# DCDC.net
KiCad netlist of a schematic drawn in Altium Designer
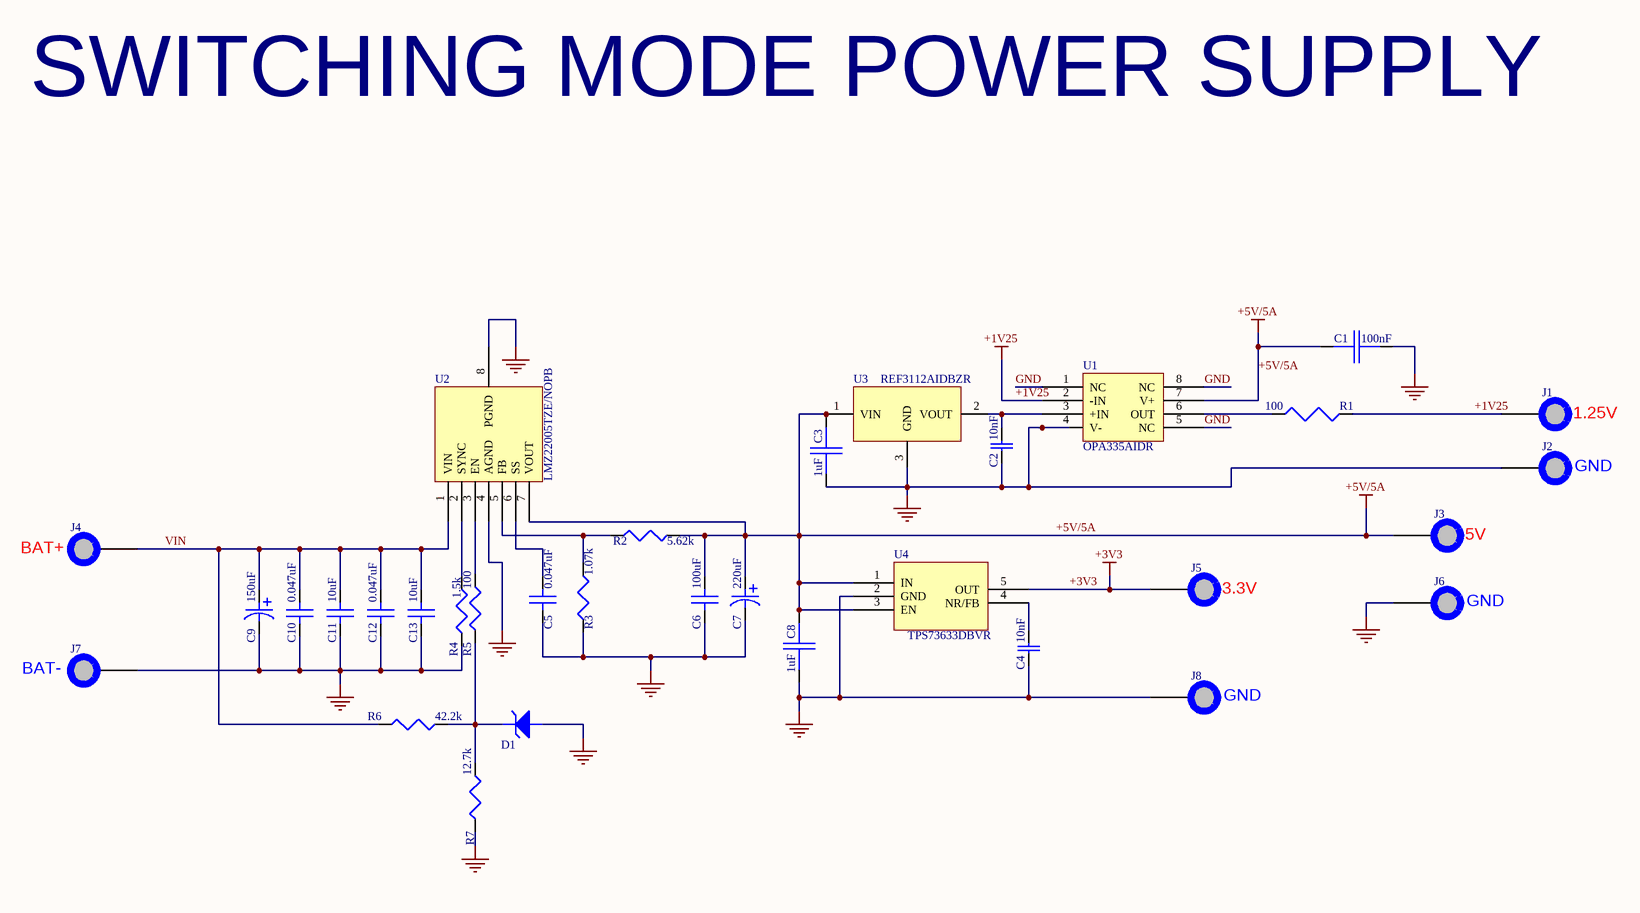
[diagram p0: DCDC.SchDoc]

(export (version "E")
  (design (tool "Eeschema 10.0.6"))
  (components
    (comp (ref "C1")
      (value "100nF")
      (footprint "C0603")
      (description "CAP CER 0.1UF 25V X7R 0603")
      (fields
        (field (name "MANUFACTURER") "Murata Electronics North America")
        (field (name "MANUFACTURER PART NUMBER") "GRM188R71E104KA01D")
      )
      (libsource (lib "EMG") (part "GRM188R71E104KA01D"))
    )
    (comp (ref "C2")
      (value "10nF")
      (footprint "C0805")
      (description "CAP CER 10000PF 50V X7R 0805")
      (fields
        (field (name "MANUFACTURER") "Murata Electronics North America")
        (field (name "MANUFACTURER PART NUMBER") "GRM216R71H103KA01D")
      )
      (libsource (lib "ISL") (part "GRM216R71H103KA01D"))
    )
    (comp (ref "C3")
      (value "1uF")
      (footprint "C0603")
      (description "CAP CER 1UF 25V X5R 0603")
      (fields
        (field (name "MANUFACTURER") "Murata Electronics North America")
        (field (name "MANUFACTURER PART NUMBER") "GRM188R61E105KA12D")
      )
      (libsource (lib "EMG") (part "GRM188R61E105KA12D"))
    )
    (comp (ref "C4")
      (value "10nF")
      (footprint "C0805")
      (description "CAP CER 10000PF 50V X7R 0805")
      (fields
        (field (name "MANUFACTURER") "Murata Electronics North America")
        (field (name "MANUFACTURER PART NUMBER") "GRM216R71H103KA01D")
      )
      (libsource (lib "ISL") (part "GRM216R71H103KA01D"))
    )
    (comp (ref "C5")
      (value "0.047uF")
      (footprint "C1206")
      (description "CAP CER 0.47UF 50V X7R 1206")
      (fields
        (field (name "MANUFACTURER") "Kemet")
        (field (name "MANUFACTURER PART NUMBER") "C1206C474K5RACTU")
      )
      (libsource (lib "DCDC") (part "C1206C474K5RACTU"))
    )
    (comp (ref "C6")
      (value "100uF")
      (footprint "C1210")
      (description "CAP CER 100UF 6.3V X5R 1210")
      (fields
        (field (name "MANUFACTURER") "TDK Corporation")
        (field (name "MANUFACTURER PART NUMBER") "C3225X5R0J107M250AC")
      )
      (libsource (lib "DCDC") (part "C3225X5R0J107M250AC"))
    )
    (comp (ref "C7")
      (value "220uF")
      (footprint "EEF-UE")
      (description "CAP POLYMER 220UF 20% 6.3V SMD")
      (fields
        (field (name "MANUFACTURER") "Panasonic Electronic Components")
        (field (name "MANUFACTURER PART NUMBER") "EEF-UE0J221LR")
      )
      (libsource (lib "DCDC") (part "EEF-UE0J221LR"))
    )
    (comp (ref "C8")
      (value "1uF")
      (footprint "C0603")
      (description "CAP CER 1UF 25V X5R 0603")
      (fields
        (field (name "MANUFACTURER") "Murata Electronics North America")
        (field (name "MANUFACTURER PART NUMBER") "GRM188R61E105KA12D")
      )
      (libsource (lib "EMG") (part "GRM188R61E105KA12D"))
    )
    (comp (ref "C9")
      (value "150uF")
      (footprint "FK-G")
      (description "CAP ALUM 150UF 20% 50V SMD")
      (fields
        (field (name "MANUFACTURER") "Panasonic Electronic Components")
        (field (name "MANUFACTURER PART NUMBER") "EEE-FK1H151P")
      )
      (libsource (lib "DCDC") (part "EEE-FK1H151P"))
    )
    (comp (ref "C10")
      (value "0.047uF")
      (footprint "C1206")
      (description "CAP CER 0.47UF 50V X7R 1206")
      (fields
        (field (name "MANUFACTURER") "Kemet")
        (field (name "MANUFACTURER PART NUMBER") "C1206C474K5RACTU")
      )
      (libsource (lib "DCDC") (part "C1206C474K5RACTU"))
    )
    (comp (ref "C11")
      (value "10uF")
      (footprint "C1206")
      (description "CAP CER 10UF 50V X5R 1206")
      (fields
        (field (name "MANUFACTURER") "Murata Electronics North America")
        (field (name "MANUFACTURER PART NUMBER") "GRM31CR61H106KA12L")
      )
      (libsource (lib "DCDC") (part "GRM31CR61H106KA12L"))
    )
    (comp (ref "C12")
      (value "0.047uF")
      (footprint "C1206")
      (description "CAP CER 0.47UF 50V X7R 1206")
      (fields
        (field (name "MANUFACTURER") "Kemet")
        (field (name "MANUFACTURER PART NUMBER") "C1206C474K5RACTU")
      )
      (libsource (lib "DCDC") (part "C1206C474K5RACTU"))
    )
    (comp (ref "C13")
      (value "10uF")
      (footprint "C1206")
      (description "CAP CER 10UF 50V X5R 1206")
      (fields
        (field (name "MANUFACTURER") "Murata Electronics North America")
        (field (name "MANUFACTURER PART NUMBER") "GRM31CR61H106KA12L")
      )
      (libsource (lib "DCDC") (part "GRM31CR61H106KA12L"))
    )
    (comp (ref "D1")
      (value "MMSZ5231BS-7-F")
      (footprint "SOD323")
      (description "DIODE ZENER 5.1V 200MW SOD323")
      (fields (field (name "MANUFACTURER") "Diodes Incorporated") (field (name "TOLERANCE") "±5%"))
      (libsource (lib "DCDC") (part "MMSZ5231BS-7-F"))
    )
    (comp (ref "J1")
      (value "PAD_4mmx1.5mm_Hole")
      (footprint "PAD_WITH_HOLE_4x1mm")
      (description "Pad 4mm x 1.5mm with hole")
      (libsource (lib "ISL") (part "PAD_4mmx1.5mm_Hole"))
    )
    (comp (ref "J2")
      (value "PAD_4mmx1.5mm_Hole")
      (footprint "PAD_WITH_HOLE_4x1mm")
      (description "Pad 4mm x 1.5mm with hole")
      (libsource (lib "ISL") (part "PAD_4mmx1.5mm_Hole"))
    )
    (comp (ref "J3")
      (value "PAD_4mmx1.5mm_Hole")
      (footprint "PAD_WITH_HOLE_4x1mm")
      (description "Pad 4mm x 1.5mm with hole")
      (libsource (lib "ISL") (part "PAD_4mmx1.5mm_Hole"))
    )
    (comp (ref "J4")
      (value "PAD_4mmx1.5mm_Hole")
      (footprint "PAD_WITH_HOLE_4x1mm")
      (description "Pad 4mm x 1.5mm with hole")
      (libsource (lib "ISL") (part "PAD_4mmx1.5mm_Hole"))
    )
    (comp (ref "J5")
      (value "PAD_4mmx1.5mm_Hole")
      (footprint "PAD_WITH_HOLE_4x1mm")
      (description "Pad 4mm x 1.5mm with hole")
      (libsource (lib "ISL") (part "PAD_4mmx1.5mm_Hole"))
    )
    (comp (ref "J6")
      (value "PAD_4mmx1.5mm_Hole")
      (footprint "PAD_WITH_HOLE_4x1mm")
      (description "Pad 4mm x 1.5mm with hole")
      (libsource (lib "ISL") (part "PAD_4mmx1.5mm_Hole"))
    )
    (comp (ref "J7")
      (value "PAD_4mmx1.5mm_Hole")
      (footprint "PAD_WITH_HOLE_4x1mm")
      (description "Pad 4mm x 1.5mm with hole")
      (libsource (lib "ISL") (part "PAD_4mmx1.5mm_Hole"))
    )
    (comp (ref "J8")
      (value "PAD_4mmx1.5mm_Hole")
      (footprint "PAD_WITH_HOLE_4x1mm")
      (description "Pad 4mm x 1.5mm with hole")
      (libsource (lib "ISL") (part "PAD_4mmx1.5mm_Hole"))
    )
    (comp (ref "R1")
      (value "100")
      (footprint "R0603")
      (description "RES SMD 100 OHM 1% 1/10W 0603")
      (fields
        (field (name "MANUFACTURER") "Panasonic Electronic Components")
        (field (name "MANUFACTURER PART NUMBER") "ERJ-3EKF1000V")
      )
      (libsource (lib "EMG") (part "ERJ-3EKF1000V"))
    )
    (comp (ref "R2")
      (value "5.62k")
      (footprint "R0805")
      (description "RES SMD 5.62K OHM 1% 1/3W 0805")
      (fields
        (field (name "MANUFACTURER") "Vishay Dale")
        (field (name "MANUFACTURER PART NUMBER") "CRCW08055K62FKEAHP")
      )
      (libsource (lib "DCDC") (part "CRCW08055K62FKEAHP"))
    )
    (comp (ref "R3")
      (value "1.07k")
      (footprint "R0805")
      (description "RES SMD 1.07K OHM 1% 1/8W 0805")
      (fields
        (field (name "MANUFACTURER") "Panasonic Electronic Components")
        (field (name "MANUFACTURER PART NUMBER") "ERJ-6ENF1071V")
      )
      (libsource (lib "DCDC") (part "ERJ-6ENF1071V"))
    )
    (comp (ref "R4")
      (value "1.5k")
      (footprint "R0805")
      (description "RES SMD 1.5K OHM 1% 1/8W 0805")
      (fields
        (field (name "MANUFACTURER") "Panasonic Electronic Components")
        (field (name "MANUFACTURER PART NUMBER") "ERJ-6ENF1501V")
      )
      (libsource (lib "DCDC") (part "ERJ-6ENF1501V"))
    )
    (comp (ref "R5")
      (value "100")
      (footprint "R0805")
      (description "RES SMD 100 OHM 1% 1/8W 0805")
      (fields
        (field (name "MANUFACTURER") "Vishay Dale")
        (field (name "MANUFACTURER PART NUMBER") "RCA0805100RFKEA")
      )
      (libsource (lib "DCDC") (part "RCA0805100RFKEA"))
    )
    (comp (ref "R6")
      (value "42.2k")
      (footprint "R0805")
      (description "RES SMD 42.2K OHM 1% 1/8W 0805")
      (fields
        (field (name "MANUFACTURER") "Panasonic Electronic Components")
        (field (name "MANUFACTURER PART NUMBER") "ERJ-6ENF4222V")
      )
      (libsource (lib "DCDC") (part "ERJ-6ENF4222V"))
    )
    (comp (ref "R7")
      (value "12.7k")
      (footprint "R0805")
      (description "RES SMD 12.7K OHM 1% 1/8W 0805")
      (fields
        (field (name "MANUFACTURER") "Panasonic Electronic Components")
        (field (name "MANUFACTURER PART NUMBER") "ERJ-6ENF1272V")
      )
      (libsource (lib "DCDC") (part "ERJ-6ENF1272V"))
    )
    (comp (ref "U1")
      (value "OPA335AIDR")
      (footprint "SO-8")
      (description "IC OPAMP CHOPPER 2MHZ RRO 8SOIC")
      (fields (field (name "MANUFACTURER") "Texas Instruments"))
      (libsource (lib "DCDC") (part "OPA335AIDR"))
    )
    (comp (ref "U2")
      (value "LMZ22005TZE/NOPB")
      (footprint "NDW0007A")
      (description "IC BUCK SYNC 20V 5A TO-PMOD-7")
      (fields (field (name "MANUFACTURER") "Texas Instruments"))
      (libsource (lib "DCDC") (part "LMZ22005TZE/NOPB"))
    )
    (comp (ref "U3")
      (value "REF3112AIDBZR")
      (footprint "SOT-23")
      (description "IC VREF SERIES 1.25V SOT23-3")
      (fields (field (name "MANUFACTURER") "Texas Instruments") (field (name "TOLERANCE") "±0.2%"))
      (libsource (lib "DCDC") (part "REF3112AIDBZR"))
    )
    (comp (ref "U4")
      (value "TPS73633DBVR")
      (footprint "SOT23-5")
      (description "IC REG LDO 3.3V 0.4A SOT23-5")
      (fields (field (name "MANUFACTURER") "Texas Instruments"))
      (libsource (lib "DCDC") (part "TPS73633DBVR"))
    )
  )
  (nets
    (net (code "1") (name "+1V25") (class "Default")
      (node (ref "J1") (pin "1") (pinfunction "1_1") (pintype "passive"))
      (node (ref "R1") (pin "1") (pinfunction "1_1") (pintype "passive"))
      (node (ref "U1") (pin "2") (pinfunction "-IN_2") (pintype "passive"))
    )
    (net (code "2") (name "+3V3") (class "Default")
      (node (ref "J5") (pin "1") (pinfunction "1_1") (pintype "passive"))
      (node (ref "U4") (pin "5") (pinfunction "OUT_5") (pintype "passive"))
    )
    (net (code "3") (name "+5V{slash}5A") (class "Default")
      (node (ref "C1") (pin "2") (pinfunction "2_2") (pintype "passive"))
      (node (ref "C3") (pin "2") (pinfunction "2_2") (pintype "passive"))
      (node (ref "C6") (pin "1") (pinfunction "1_1") (pintype "passive"))
      (node (ref "C7") (pin "1") (pinfunction "1_1") (pintype "passive"))
      (node (ref "C8") (pin "2") (pinfunction "2_2") (pintype "passive"))
      (node (ref "J3") (pin "1") (pinfunction "1_1") (pintype "passive"))
      (node (ref "R2") (pin "2") (pinfunction "2_2") (pintype "passive"))
      (node (ref "U1") (pin "7") (pinfunction "V+_7") (pintype "passive"))
      (node (ref "U2") (pin "7") (pinfunction "VOUT_7") (pintype "passive"))
      (node (ref "U3") (pin "1") (pinfunction "VIN_1") (pintype "passive"))
      (node (ref "U4") (pin "1") (pinfunction "IN_1") (pintype "passive"))
      (node (ref "U4") (pin "3") (pinfunction "EN_3") (pintype "passive"))
    )
    (net (code "4") (name "/VIN") (class "Default")
      (node (ref "C10") (pin "1") (pinfunction "1_1") (pintype "passive"))
      (node (ref "C11") (pin "2") (pinfunction "2_2") (pintype "passive"))
      (node (ref "C12") (pin "1") (pinfunction "1_1") (pintype "passive"))
      (node (ref "C13") (pin "2") (pinfunction "2_2") (pintype "passive"))
      (node (ref "C9") (pin "1") (pinfunction "1_1") (pintype "passive"))
      (node (ref "J4") (pin "1") (pinfunction "1_1") (pintype "passive"))
      (node (ref "R6") (pin "1") (pinfunction "1_1") (pintype "passive"))
      (node (ref "U2") (pin "1") (pinfunction "VIN_1") (pintype "passive"))
    )
    (net (code "5") (name "GND") (class "Default")
      (node (ref "C1") (pin "1") (pinfunction "1_1") (pintype "passive"))
      (node (ref "C10") (pin "2") (pinfunction "2_2") (pintype "passive"))
      (node (ref "C11") (pin "1") (pinfunction "1_1") (pintype "passive"))
      (node (ref "C12") (pin "2") (pinfunction "2_2") (pintype "passive"))
      (node (ref "C13") (pin "1") (pinfunction "1_1") (pintype "passive"))
      (node (ref "C2") (pin "1") (pinfunction "1_1") (pintype "passive"))
      (node (ref "C3") (pin "1") (pinfunction "1_1") (pintype "passive"))
      (node (ref "C4") (pin "1") (pinfunction "1_1") (pintype "passive"))
      (node (ref "C5") (pin "2") (pinfunction "2_2") (pintype "passive"))
      (node (ref "C6") (pin "2") (pinfunction "2_2") (pintype "passive"))
      (node (ref "C7") (pin "2") (pinfunction "2_2") (pintype "passive"))
      (node (ref "C8") (pin "1") (pinfunction "1_1") (pintype "passive"))
      (node (ref "C9") (pin "2") (pinfunction "2_2") (pintype "passive"))
      (node (ref "D1") (pin "1") (pinfunction "1_1") (pintype "passive"))
      (node (ref "J2") (pin "1") (pinfunction "1_1") (pintype "passive"))
      (node (ref "J6") (pin "1") (pinfunction "1_1") (pintype "passive"))
      (node (ref "J7") (pin "1") (pinfunction "1_1") (pintype "passive"))
      (node (ref "J8") (pin "1") (pinfunction "1_1") (pintype "passive"))
      (node (ref "R3") (pin "1") (pinfunction "1_1") (pintype "passive"))
      (node (ref "R4") (pin "1") (pinfunction "1_1") (pintype "passive"))
      (node (ref "R7") (pin "2") (pinfunction "2_2") (pintype "passive"))
      (node (ref "U1") (pin "1") (pinfunction "NC_1") (pintype "passive"))
      (node (ref "U1") (pin "4") (pinfunction "V-_4") (pintype "passive"))
      (node (ref "U1") (pin "5") (pinfunction "NC_5") (pintype "passive"))
      (node (ref "U1") (pin "8") (pinfunction "NC_8") (pintype "passive"))
      (node (ref "U2") (pin "4") (pinfunction "AGND_4") (pintype "passive"))
      (node (ref "U2") (pin "8") (pinfunction "PGND_8") (pintype "passive"))
      (node (ref "U3") (pin "3") (pinfunction "GND_3") (pintype "passive"))
      (node (ref "U4") (pin "2") (pinfunction "GND_2") (pintype "passive"))
    )
    (net (code "6") (name "Net-(D1-Pad2)") (class "Default")
      (node (ref "D1") (pin "2") (pinfunction "2_2") (pintype "passive"))
      (node (ref "R5") (pin "1") (pinfunction "1_1") (pintype "passive"))
      (node (ref "R6") (pin "2") (pinfunction "2_2") (pintype "passive"))
      (node (ref "R7") (pin "1") (pinfunction "1_1") (pintype "passive"))
    )
    (net (code "7") (name "Net-(U1-+IN)") (class "Default")
      (node (ref "C2") (pin "2") (pinfunction "2_2") (pintype "passive"))
      (node (ref "U1") (pin "3") (pinfunction "+IN_3") (pintype "passive"))
      (node (ref "U3") (pin "2") (pinfunction "VOUT_2") (pintype "passive"))
    )
    (net (code "8") (name "Net-(U1-OUT)") (class "Default")
      (node (ref "R1") (pin "2") (pinfunction "2_2") (pintype "passive"))
      (node (ref "U1") (pin "6") (pinfunction "OUT_6") (pintype "passive"))
    )
    (net (code "9") (name "Net-(U2-EN)") (class "Default")
      (node (ref "R5") (pin "2") (pinfunction "2_2") (pintype "passive"))
      (node (ref "U2") (pin "3") (pinfunction "EN_3") (pintype "passive"))
    )
    (net (code "10") (name "Net-(U2-FB)") (class "Default")
      (node (ref "R2") (pin "1") (pinfunction "1_1") (pintype "passive"))
      (node (ref "R3") (pin "2") (pinfunction "2_2") (pintype "passive"))
      (node (ref "U2") (pin "5") (pinfunction "FB_5") (pintype "passive"))
    )
    (net (code "11") (name "Net-(U2-SS)") (class "Default")
      (node (ref "C5") (pin "1") (pinfunction "1_1") (pintype "passive"))
      (node (ref "U2") (pin "6") (pinfunction "SS_6") (pintype "passive"))
    )
    (net (code "12") (name "Net-(U2-SYNC)") (class "Default")
      (node (ref "R4") (pin "2") (pinfunction "2_2") (pintype "passive"))
      (node (ref "U2") (pin "2") (pinfunction "SYNC_2") (pintype "passive"))
    )
    (net (code "13") (name "Net-(U4-NR{slash}FB)") (class "Default")
      (node (ref "C4") (pin "2") (pinfunction "2_2") (pintype "passive"))
      (node (ref "U4") (pin "4") (pinfunction "NR/FB_4") (pintype "passive"))
    )
  )
)
